# bga614_lna.net
KiCad netlist of a schematic drawn in EAGLE
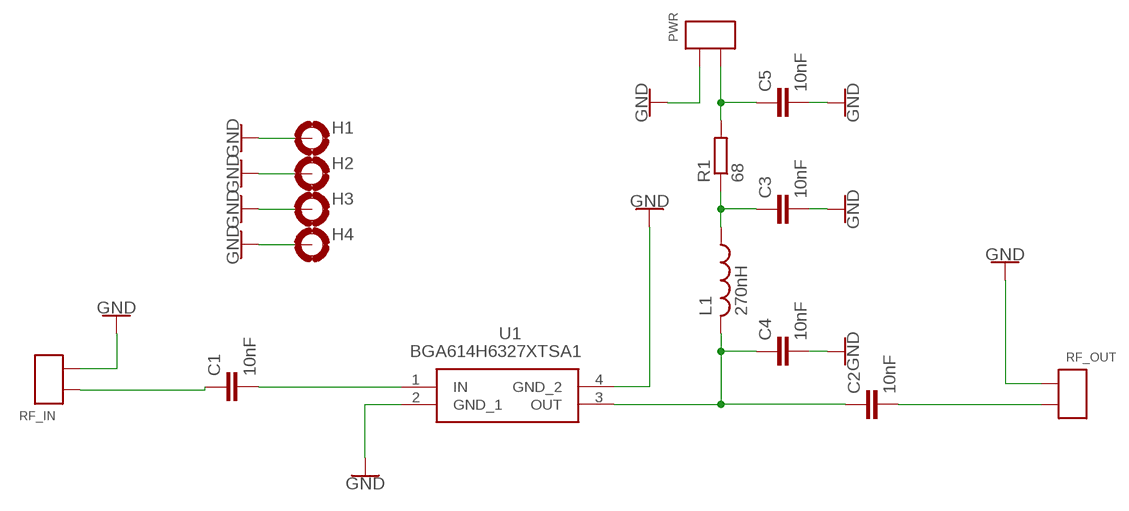
[diagram p0: schematic, sheet 1]

(export (version "E")
  (design (tool "Eeschema 10.0.6"))
  (components
    (comp (ref "C1")
      (value "10nF")
      (footprint "eagle-import:C0805K")
      (libsource (lib "eagle-import") (part "C_0805_PTH"))
    )
    (comp (ref "C2")
      (value "10nF")
      (footprint "eagle-import:C0805K")
      (libsource (lib "eagle-import") (part "C_0805_PTH"))
    )
    (comp (ref "C3")
      (value "10nF")
      (footprint "eagle-import:C0805K")
      (libsource (lib "eagle-import") (part "C_0805_PTH"))
    )
    (comp (ref "C4")
      (value "10nF")
      (footprint "eagle-import:C0805K")
      (libsource (lib "eagle-import") (part "C_0805_PTH"))
    )
    (comp (ref "C5")
      (value "10nF")
      (footprint "eagle-import:C0805K")
      (libsource (lib "eagle-import") (part "C_0805_PTH"))
    )
    (comp (ref "H1")
      (value "MOUNT-PAD-ROUND3.0")
      (footprint "eagle-import:3,0-PAD")
      (libsource (lib "eagle-import") (part "MOUNT-PAD-ROUND3.0"))
    )
    (comp (ref "H2")
      (value "MOUNT-PAD-ROUND3.0")
      (footprint "eagle-import:3,0-PAD")
      (libsource (lib "eagle-import") (part "MOUNT-PAD-ROUND3.0"))
    )
    (comp (ref "H3")
      (value "MOUNT-PAD-ROUND3.0")
      (footprint "eagle-import:3,0-PAD")
      (libsource (lib "eagle-import") (part "MOUNT-PAD-ROUND3.0"))
    )
    (comp (ref "H4")
      (value "MOUNT-PAD-ROUND3.0")
      (footprint "eagle-import:3,0-PAD")
      (libsource (lib "eagle-import") (part "MOUNT-PAD-ROUND3.0"))
    )
    (comp (ref "L1")
      (value "270nH")
      (footprint "eagle-import:M0805")
      (libsource (lib "eagle-import") (part "L_0805_PTH"))
    )
    (comp (ref "PWR")
      (value "2X_SMD_PTH_PIN")
      (footprint "eagle-import:2X_SMD_PTH")
      (libsource (lib "eagle-import") (part "2X_SMD_PTH_PIN"))
    )
    (comp (ref "R1")
      (value "68")
      (footprint "eagle-import:R0805W")
      (libsource (lib "eagle-import") (part "R_0805_SMD"))
    )
    (comp (ref "RF_IN")
      (value "2X_SMD_PTH_PIN")
      (footprint "eagle-import:2X_SMD_PTH")
      (libsource (lib "eagle-import") (part "2X_SMD_PTH_PIN"))
    )
    (comp (ref "RF_OUT")
      (value "2X_SMD_PTH_PIN")
      (footprint "eagle-import:2X_SMD_PTH")
      (libsource (lib "eagle-import") (part "2X_SMD_PTH_PIN"))
    )
    (comp (ref "U1")
      (value "BGA614H6327XTSA1")
      (footprint "eagle-import:BGA614H6327XTSA1")
      (fields (field (name "MOUSER_PART_NUMBER") "726-BGA614H6327XTSA1"))
      (libsource (lib "eagle-import") (part "BGA614H6327XTSA1"))
    )
  )
  (nets
    (net (code "1") (name "GND") (class "Default")
      (node (ref "C3") (pin "2") (pinfunction "2_2") (pintype "passive"))
      (node (ref "C3") (pin "P$2") (pinfunction "2_P$2") (pintype "passive"))
      (node (ref "C4") (pin "2") (pinfunction "2_2") (pintype "passive"))
      (node (ref "C4") (pin "P$2") (pinfunction "2_P$2") (pintype "passive"))
      (node (ref "C5") (pin "2") (pinfunction "2_2") (pintype "passive"))
      (node (ref "C5") (pin "P$2") (pinfunction "2_P$2") (pintype "passive"))
      (node (ref "H1") (pin "B3,0") (pinfunction "MOUNT_B3,0") (pintype "passive"))
      (node (ref "H2") (pin "B3,0") (pinfunction "MOUNT_B3,0") (pintype "passive"))
      (node (ref "H3") (pin "B3,0") (pinfunction "MOUNT_B3,0") (pintype "passive"))
      (node (ref "H4") (pin "B3,0") (pinfunction "MOUNT_B3,0") (pintype "passive"))
      (node (ref "PWR") (pin "P$1") (pinfunction "PIN0_P$1") (pintype "bidirectional"))
      (node (ref "PWR") (pin "T$1") (pinfunction "PIN0_T$1") (pintype "bidirectional"))
      (node (ref "RF_IN") (pin "P$2") (pinfunction "PIN1_P$2") (pintype "bidirectional"))
      (node (ref "RF_IN") (pin "T$2") (pinfunction "PIN1_T$2") (pintype "bidirectional"))
      (node (ref "RF_OUT") (pin "P$1") (pinfunction "PIN0_P$1") (pintype "bidirectional"))
      (node (ref "RF_OUT") (pin "T$1") (pinfunction "PIN0_T$1") (pintype "bidirectional"))
      (node (ref "U1") (pin "2") (pinfunction "GND_1_2") (pintype "bidirectional"))
      (node (ref "U1") (pin "4") (pinfunction "GND_2_4") (pintype "bidirectional"))
    )
    (net (code "2") (name "Net-(C1-1-PadP$1)") (class "Default")
      (node (ref "C1") (pin "1") (pinfunction "1_1") (pintype "passive"))
      (node (ref "C1") (pin "P$1") (pinfunction "1_P$1") (pintype "passive"))
      (node (ref "RF_IN") (pin "P$1") (pinfunction "PIN0_P$1") (pintype "bidirectional"))
      (node (ref "RF_IN") (pin "T$1") (pinfunction "PIN0_T$1") (pintype "bidirectional"))
    )
    (net (code "3") (name "Net-(C2-2-PadP$2)") (class "Default")
      (node (ref "C2") (pin "2") (pinfunction "2_2") (pintype "passive"))
      (node (ref "C2") (pin "P$2") (pinfunction "2_P$2") (pintype "passive"))
      (node (ref "RF_OUT") (pin "P$2") (pinfunction "PIN1_P$2") (pintype "bidirectional"))
      (node (ref "RF_OUT") (pin "T$2") (pinfunction "PIN1_T$2") (pintype "bidirectional"))
    )
    (net (code "4") (name "Net-(C3-1-PadP$1)") (class "Default")
      (node (ref "C3") (pin "1") (pinfunction "1_1") (pintype "passive"))
      (node (ref "C3") (pin "P$1") (pinfunction "1_P$1") (pintype "passive"))
      (node (ref "L1") (pin "1") (pinfunction "1_1") (pintype "passive"))
      (node (ref "L1") (pin "P$1") (pinfunction "1_P$1") (pintype "passive"))
      (node (ref "R1") (pin "1") (pinfunction "1_1") (pintype "passive"))
    )
    (net (code "5") (name "Net-(C5-1-PadP$1)") (class "Default")
      (node (ref "C5") (pin "1") (pinfunction "1_1") (pintype "passive"))
      (node (ref "C5") (pin "P$1") (pinfunction "1_P$1") (pintype "passive"))
      (node (ref "PWR") (pin "P$2") (pinfunction "PIN1_P$2") (pintype "bidirectional"))
      (node (ref "PWR") (pin "T$2") (pinfunction "PIN1_T$2") (pintype "bidirectional"))
      (node (ref "R1") (pin "2") (pinfunction "2_2") (pintype "passive"))
    )
    (net (code "6") (name "Net-(U1-IN)") (class "Default")
      (node (ref "C1") (pin "2") (pinfunction "2_2") (pintype "passive"))
      (node (ref "C1") (pin "P$2") (pinfunction "2_P$2") (pintype "passive"))
      (node (ref "U1") (pin "1") (pinfunction "IN_1") (pintype "bidirectional"))
    )
    (net (code "7") (name "Net-(U1-OUT)") (class "Default")
      (node (ref "C2") (pin "1") (pinfunction "1_1") (pintype "passive"))
      (node (ref "C2") (pin "P$1") (pinfunction "1_P$1") (pintype "passive"))
      (node (ref "C4") (pin "1") (pinfunction "1_1") (pintype "passive"))
      (node (ref "C4") (pin "P$1") (pinfunction "1_P$1") (pintype "passive"))
      (node (ref "L1") (pin "2") (pinfunction "2_2") (pintype "passive"))
      (node (ref "L1") (pin "P$2") (pinfunction "2_P$2") (pintype "passive"))
      (node (ref "U1") (pin "3") (pinfunction "OUT_3") (pintype "bidirectional"))
    )
  )
)
